# 08_FPGA_D.net
KiCad netlist of a schematic drawn in Altium Designer
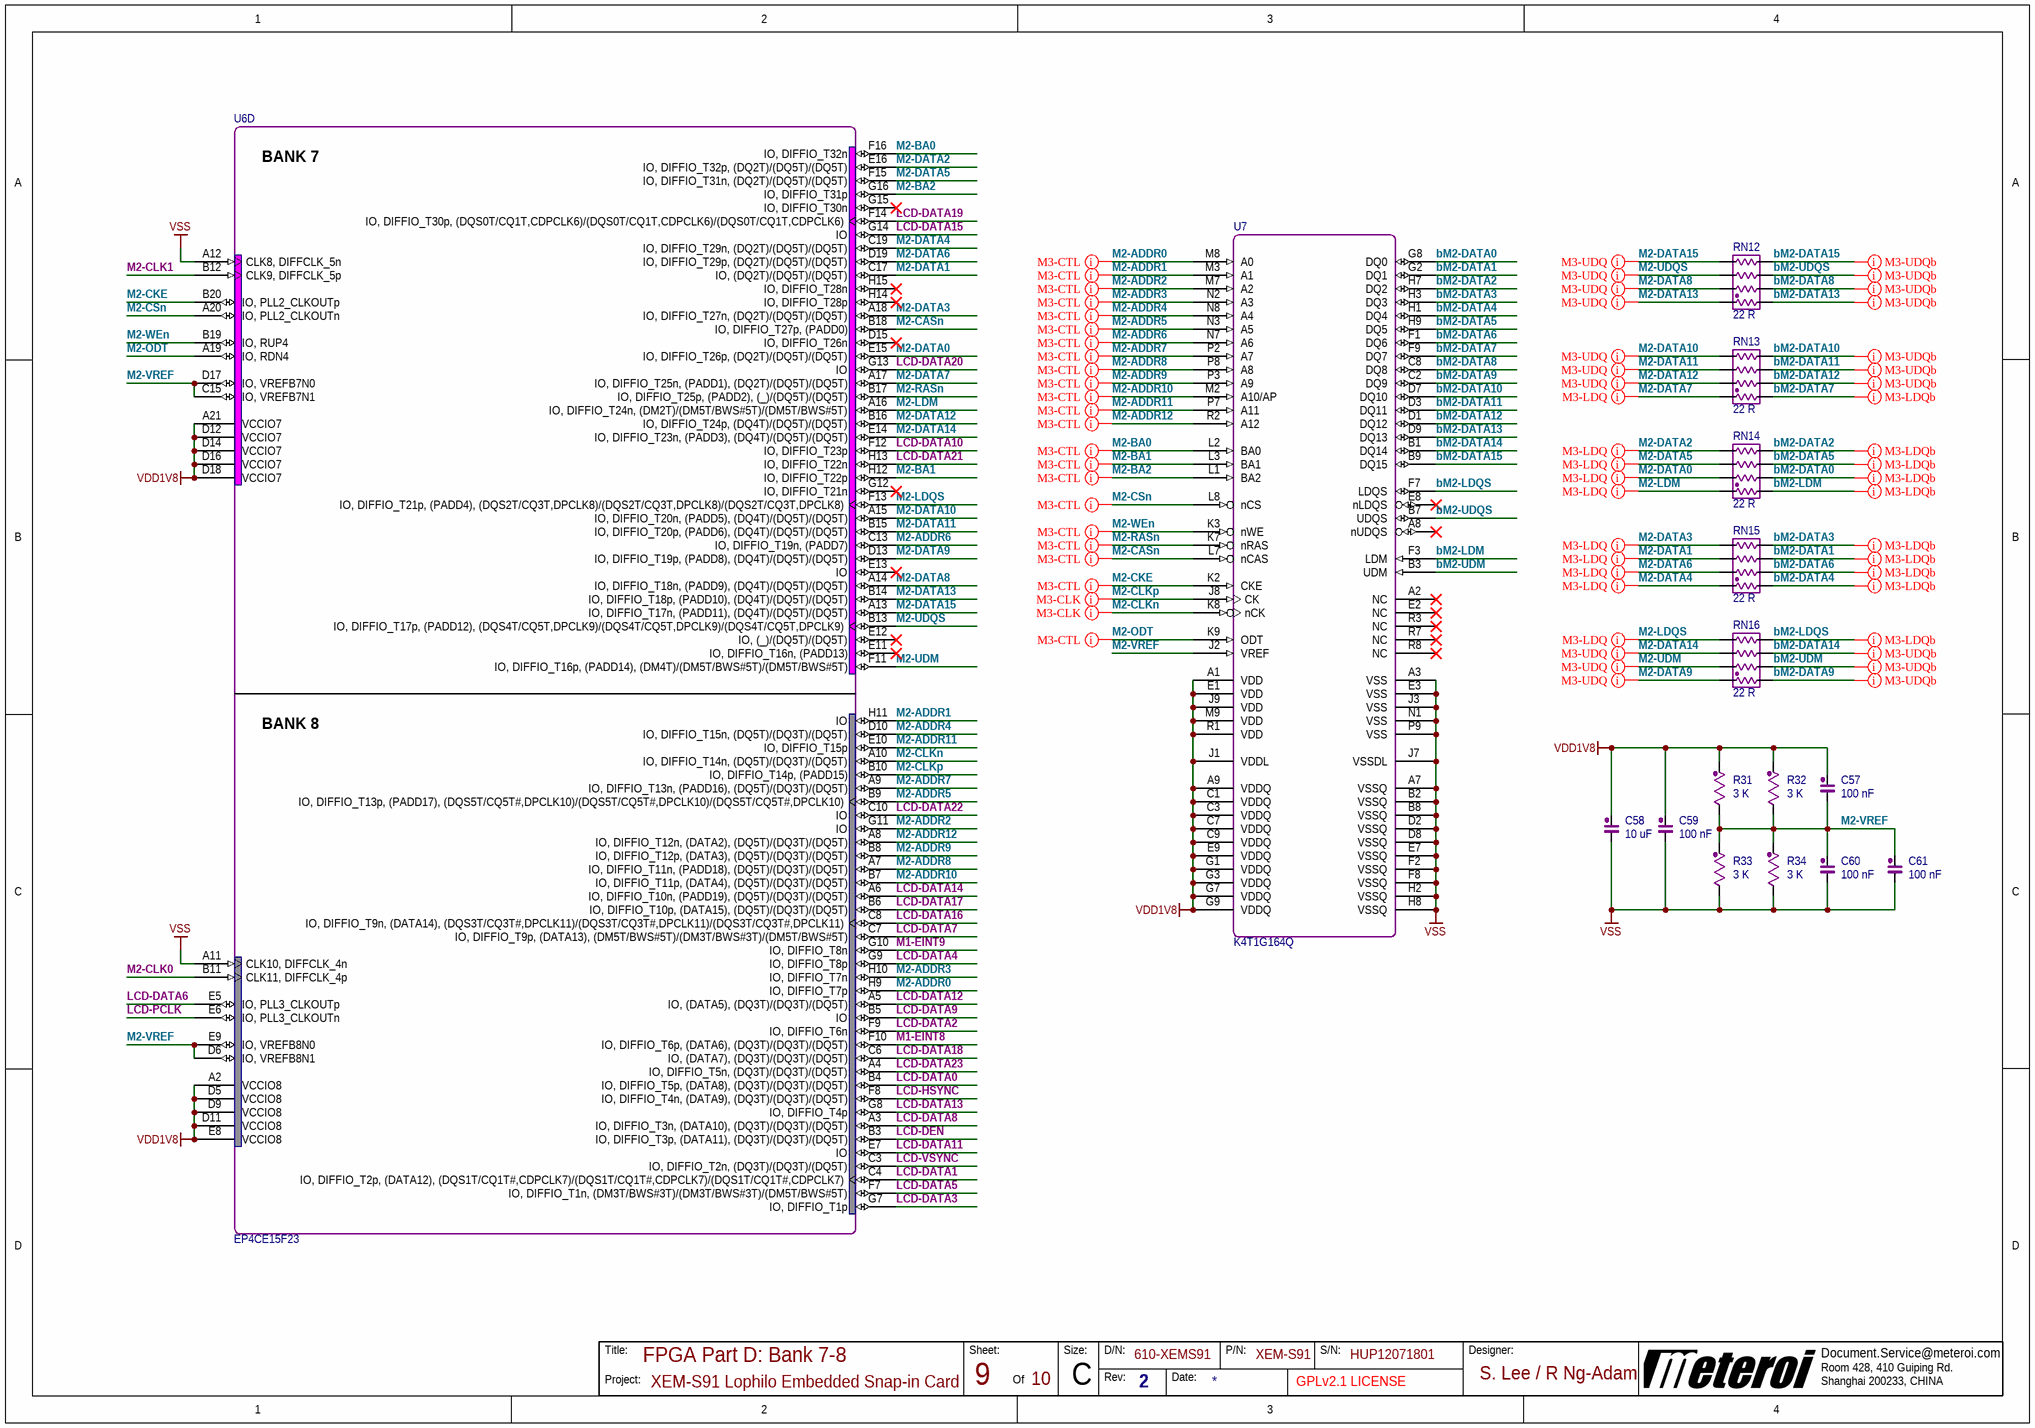
[diagram p0: 08_FPGA_D.SchDoc]

(export (version "E")
  (design (tool "Eeschema 10.0.6"))
  (components
    (comp (ref "C57")
      (value "100 nF")
      (footprint "0402A1")
      (description "Normal Capacitor")
      (fields
        (field (name "PARTNUMBER") "0")
        (field (name "PUBLISHER") "Cowin")
        (field (name "DESIGNER") "shyul")
      )
      (libsource (lib "Basc_1_Passive") (part "CAP"))
    )
    (comp (ref "C58")
      (value "10 uF")
      (footprint "0603A1")
      (description "Normal Capacitor")
      (fields
        (field (name "PARTNUMBER") "0")
        (field (name "PUBLISHER") "Cowin")
        (field (name "DESIGNER") "shyul")
      )
      (libsource (lib "Basc_1_Passive") (part "CAP"))
    )
    (comp (ref "C59")
      (value "100 nF")
      (footprint "0402A1")
      (description "Normal Capacitor")
      (fields
        (field (name "PARTNUMBER") "0")
        (field (name "PUBLISHER") "Cowin")
        (field (name "DESIGNER") "shyul")
      )
      (libsource (lib "Basc_1_Passive") (part "CAP"))
    )
    (comp (ref "C60")
      (value "100 nF")
      (footprint "0402A1")
      (description "Normal Capacitor")
      (fields
        (field (name "PARTNUMBER") "0")
        (field (name "PUBLISHER") "Cowin")
        (field (name "DESIGNER") "shyul")
      )
      (libsource (lib "Basc_1_Passive") (part "CAP"))
    )
    (comp (ref "C61")
      (value "100 nF")
      (footprint "0402BG")
      (description "Normal Capacitor")
      (fields
        (field (name "PARTNUMBER") "0")
        (field (name "PUBLISHER") "Cowin")
        (field (name "DESIGNER") "shyul")
      )
      (libsource (lib "Basc_1_Passive") (part "CAP"))
    )
    (comp (ref "R31")
      (value "3 K")
      (footprint "0402A2")
      (description "Normal Resistor")
      (fields
        (field (name "PARTNUMBER") "0")
        (field (name "DESIGNER") "shyul")
        (field (name "PUBLISHER") "Cowin")
      )
      (libsource (lib "Basc_1_Passive") (part "RES"))
    )
    (comp (ref "R32")
      (value "3 K")
      (footprint "0402A2")
      (description "Normal Resistor")
      (fields
        (field (name "PARTNUMBER") "0")
        (field (name "DESIGNER") "shyul")
        (field (name "PUBLISHER") "Cowin")
      )
      (libsource (lib "Basc_1_Passive") (part "RES"))
    )
    (comp (ref "R33")
      (value "3 K")
      (footprint "0402A2")
      (description "Normal Resistor")
      (fields
        (field (name "PARTNUMBER") "0")
        (field (name "DESIGNER") "shyul")
        (field (name "PUBLISHER") "Cowin")
      )
      (libsource (lib "Basc_1_Passive") (part "RES"))
    )
    (comp (ref "R34")
      (value "3 K")
      (footprint "0402A2")
      (description "Normal Resistor")
      (fields
        (field (name "PARTNUMBER") "0")
        (field (name "DESIGNER") "shyul")
        (field (name "PUBLISHER") "Cowin")
      )
      (libsource (lib "Basc_1_Passive") (part "RES"))
    )
    (comp (ref "RN12")
      (value "22 R")
      (footprint "0402PR4")
      (description "Resistor Array x4")
      (fields
        (field (name "PARTNUMBER") "YC124-JR-0722RL")
        (field (name "PUBLISHER") "Cowin")
        (field (name "DESIGNER") "shyul")
      )
      (libsource (lib "Basc_1_Passive") (part "RES_N4"))
    )
    (comp (ref "RN13")
      (value "22 R")
      (footprint "0402PR4")
      (description "Resistor Array x4")
      (fields
        (field (name "PARTNUMBER") "YC124-JR-0722RL")
        (field (name "PUBLISHER") "Cowin")
        (field (name "DESIGNER") "shyul")
      )
      (libsource (lib "Basc_1_Passive") (part "RES_N4"))
    )
    (comp (ref "RN14")
      (value "22 R")
      (footprint "0402PR4")
      (description "Resistor Array x4")
      (fields
        (field (name "PARTNUMBER") "YC124-JR-0722RL")
        (field (name "PUBLISHER") "Cowin")
        (field (name "DESIGNER") "shyul")
      )
      (libsource (lib "Basc_1_Passive") (part "RES_N4"))
    )
    (comp (ref "RN15")
      (value "22 R")
      (footprint "0402PR4")
      (description "Resistor Array x4")
      (fields
        (field (name "PARTNUMBER") "YC124-JR-0722RL")
        (field (name "PUBLISHER") "Cowin")
        (field (name "DESIGNER") "shyul")
      )
      (libsource (lib "Basc_1_Passive") (part "RES_N4"))
    )
    (comp (ref "RN16")
      (value "22 R")
      (footprint "0402PR4")
      (description "Resistor Array x4")
      (fields
        (field (name "PARTNUMBER") "YC124-JR-0722RL")
        (field (name "PUBLISHER") "Cowin")
        (field (name "DESIGNER") "shyul")
      )
      (libsource (lib "Basc_1_Passive") (part "RES_N4"))
    )
    (comp (ref "U6")
      (value "EP4CE15F23")
      (footprint "FBGA-484")
      (description "Cyclone IV EP4CE15F23 FPGA")
      (fields
        (field (name "PARTNUMBER") "EP4CE15F23C8N")
        (field (name "DESIGNER") "shyul")
        (field (name "PUBLISHER") "Cowin")
      )
      (libsource (lib "PCB_XEM-S91") (part "EP4CE15F23"))
    )
    (comp (ref "U7")
      (value "K4T1G164Q")
      (footprint "FBGA-DDR-84")
      (description "K4T1G164Q 64M x16 DDR2 SDRAM")
      (fields
        (field (name "PARTNUMBER") "K4T1G164QF-BCE7")
        (field (name "DESIGNER") "shyul")
        (field (name "PUBLISHER") "Cowin")
      )
      (libsource (lib "PCB_XEM-S91") (part "K4T1G164Q"))
    )
  )
  (nets
    (net (code "1") (name "/LCD-DATA0") (class "Default")
      (node (ref "U6") (pin "B4") (pinfunction "IO,_DIFFIO_T5p,_(DATA8),_(DQ3T)/(DQ3T)/(DQ5T)_B4") (pintype "bidirectional"))
    )
    (net (code "2") (name "/LCD-DATA1") (class "Default")
      (node (ref "U6") (pin "C4") (pinfunction "IO,_DIFFIO_T2p,_(DATA12),_(DQS1T/CQ1T#,CDPCLK7)/(DQS1T/CQ1T#,CDPCLK7)/(DQS1T/CQ1T#,CDPCLK7)_C4") (pintype "bidirectional"))
    )
    (net (code "3") (name "/LCD-DATA2") (class "Default")
      (node (ref "U6") (pin "F9") (pinfunction "IO,_DIFFIO_T6n_F9") (pintype "bidirectional"))
    )
    (net (code "4") (name "/LCD-DATA3") (class "Default")
      (node (ref "U6") (pin "G7") (pinfunction "IO,_DIFFIO_T1p_G7") (pintype "bidirectional"))
    )
    (net (code "5") (name "/LCD-DATA4") (class "Default")
      (node (ref "U6") (pin "G9") (pinfunction "IO,_DIFFIO_T8p_G9") (pintype "bidirectional"))
    )
    (net (code "6") (name "/LCD-DATA5") (class "Default")
      (node (ref "U6") (pin "F7") (pinfunction "IO,_DIFFIO_T1n,_(DM3T/BWS#3T)/(DM3T/BWS#3T)/(DM5T/BWS#5T)_F7") (pintype "bidirectional"))
    )
    (net (code "7") (name "/LCD-DATA6") (class "Default")
      (node (ref "U6") (pin "E5") (pinfunction "IO,_PLL3_CLKOUTp_E5") (pintype "bidirectional"))
    )
    (net (code "8") (name "/LCD-DATA7") (class "Default")
      (node (ref "U6") (pin "C7") (pinfunction "IO,_DIFFIO_T9p,_(DATA13),_(DM5T/BWS#5T)/(DM3T/BWS#3T)/(DM5T/BWS#5T)_C7") (pintype "bidirectional"))
    )
    (net (code "9") (name "/LCD-DATA8") (class "Default")
      (node (ref "U6") (pin "A3") (pinfunction "IO,_DIFFIO_T3n,_(DATA10),_(DQ3T)/(DQ3T)/(DQ5T)_A3") (pintype "bidirectional"))
    )
    (net (code "10") (name "/LCD-DATA9") (class "Default")
      (node (ref "U6") (pin "B5") (pinfunction "IO_B5") (pintype "bidirectional"))
    )
    (net (code "11") (name "/LCD-DATA10") (class "Default")
      (node (ref "U6") (pin "F12") (pinfunction "IO,_DIFFIO_T23p_F12") (pintype "bidirectional"))
    )
    (net (code "12") (name "/LCD-DATA11") (class "Default")
      (node (ref "U6") (pin "E7") (pinfunction "IO_E7") (pintype "bidirectional"))
    )
    (net (code "13") (name "/LCD-DATA12") (class "Default")
      (node (ref "U6") (pin "A5") (pinfunction "IO,_(DATA5),_(DQ3T)/(DQ3T)/(DQ5T)_A5") (pintype "bidirectional"))
    )
    (net (code "14") (name "/LCD-DATA13") (class "Default")
      (node (ref "U6") (pin "G8") (pinfunction "IO,_DIFFIO_T4p_G8") (pintype "bidirectional"))
    )
    (net (code "15") (name "/LCD-DATA14") (class "Default")
      (node (ref "U6") (pin "A6") (pinfunction "IO,_DIFFIO_T10n,_(PADD19),_(DQ5T)/(DQ3T)/(DQ5T)_A6") (pintype "bidirectional"))
    )
    (net (code "16") (name "/LCD-DATA15") (class "Default")
      (node (ref "U6") (pin "G14") (pinfunction "IO_G14") (pintype "bidirectional"))
    )
    (net (code "17") (name "/LCD-DATA16") (class "Default")
      (node (ref "U6") (pin "C8") (pinfunction "IO,_DIFFIO_T9n,_(DATA14),_(DQS3T/CQ3T#,DPCLK11)/(DQS3T/CQ3T#,DPCLK11)/(DQS3T/CQ3T#,DPCLK11)_C8") (pintype "bidirectional"))
    )
    (net (code "18") (name "/LCD-DATA17") (class "Default")
      (node (ref "U6") (pin "B6") (pinfunction "IO,_DIFFIO_T10p,_(DATA15),_(DQ5T)/(DQ3T)/(DQ5T)_B6") (pintype "bidirectional"))
    )
    (net (code "19") (name "/LCD-DATA18") (class "Default")
      (node (ref "U6") (pin "C6") (pinfunction "IO,_(DATA7),_(DQ3T)/(DQ3T)/(DQ5T)_C6") (pintype "bidirectional"))
    )
    (net (code "20") (name "/LCD-DATA19") (class "Default")
      (node (ref "U6") (pin "F14") (pinfunction "IO,_DIFFIO_T30p,_(DQS0T/CQ1T,CDPCLK6)/(DQS0T/CQ1T,CDPCLK6)/(DQS0T/CQ1T,CDPCLK6)_F14") (pintype "bidirectional"))
    )
    (net (code "21") (name "/LCD-DATA20") (class "Default")
      (node (ref "U6") (pin "G13") (pinfunction "IO_G13") (pintype "bidirectional"))
    )
    (net (code "22") (name "/LCD-DATA21") (class "Default")
      (node (ref "U6") (pin "H13") (pinfunction "IO,_DIFFIO_T22n_H13") (pintype "bidirectional"))
    )
    (net (code "23") (name "/LCD-DATA22") (class "Default")
      (node (ref "U6") (pin "C10") (pinfunction "IO_C10") (pintype "bidirectional"))
    )
    (net (code "24") (name "/LCD-DATA23") (class "Default")
      (node (ref "U6") (pin "A4") (pinfunction "IO,_DIFFIO_T5n,_(DQ3T)/(DQ3T)/(DQ5T)_A4") (pintype "bidirectional"))
    )
    (net (code "25") (name "/LCD-DEN") (class "Default")
      (node (ref "U6") (pin "B3") (pinfunction "IO,_DIFFIO_T3p,_(DATA11),_(DQ3T)/(DQ3T)/(DQ5T)_B3") (pintype "bidirectional"))
    )
    (net (code "26") (name "/LCD-HSYNC") (class "Default")
      (node (ref "U6") (pin "F8") (pinfunction "IO,_DIFFIO_T4n,_(DATA9),_(DQ3T)/(DQ3T)/(DQ5T)_F8") (pintype "bidirectional"))
    )
    (net (code "27") (name "/LCD-PCLK") (class "Default")
      (node (ref "U6") (pin "E6") (pinfunction "IO,_PLL3_CLKOUTn_E6") (pintype "bidirectional"))
    )
    (net (code "28") (name "/LCD-VSYNC") (class "Default")
      (node (ref "U6") (pin "C3") (pinfunction "IO,_DIFFIO_T2n,_(DQ3T)/(DQ3T)/(DQ5T)_C3") (pintype "bidirectional"))
    )
    (net (code "29") (name "/M1-EINT8") (class "Default")
      (node (ref "U6") (pin "F10") (pinfunction "IO,_DIFFIO_T6p,_(DATA6),_(DQ3T)/(DQ3T)/(DQ5T)_F10") (pintype "bidirectional"))
    )
    (net (code "30") (name "/M1-EINT9") (class "Default")
      (node (ref "U6") (pin "G10") (pinfunction "IO,_DIFFIO_T8n_G10") (pintype "bidirectional"))
    )
    (net (code "31") (name "/M2-ADDR0") (class "Default")
      (node (ref "U6") (pin "H9") (pinfunction "IO,_DIFFIO_T7p_H9") (pintype "bidirectional"))
      (node (ref "U7") (pin "M8") (pinfunction "A0_M8") (pintype "input"))
    )
    (net (code "32") (name "/M2-ADDR1") (class "Default")
      (node (ref "U6") (pin "H11") (pinfunction "IO_H11") (pintype "bidirectional"))
      (node (ref "U7") (pin "M3") (pinfunction "A1_M3") (pintype "input"))
    )
    (net (code "33") (name "/M2-ADDR2") (class "Default")
      (node (ref "U6") (pin "G11") (pinfunction "IO_G11") (pintype "bidirectional"))
      (node (ref "U7") (pin "M7") (pinfunction "A2_M7") (pintype "input"))
    )
    (net (code "34") (name "/M2-ADDR3") (class "Default")
      (node (ref "U6") (pin "H10") (pinfunction "IO,_DIFFIO_T7n_H10") (pintype "bidirectional"))
      (node (ref "U7") (pin "N2") (pinfunction "A3_N2") (pintype "input"))
    )
    (net (code "35") (name "/M2-ADDR4") (class "Default")
      (node (ref "U6") (pin "D10") (pinfunction "IO,_DIFFIO_T15n,_(DQ5T)/(DQ3T)/(DQ5T)_D10") (pintype "bidirectional"))
      (node (ref "U7") (pin "N8") (pinfunction "A4_N8") (pintype "input"))
    )
    (net (code "36") (name "/M2-ADDR5") (class "Default")
      (node (ref "U6") (pin "B9") (pinfunction "IO,_DIFFIO_T13p,_(PADD17),_(DQS5T/CQ5T#,DPCLK10)/(DQS5T/CQ5T#,DPCLK10)/(DQS5T/CQ5T#,DPCLK10)_B9") (pintype "bidirectional"))
      (node (ref "U7") (pin "N3") (pinfunction "A5_N3") (pintype "input"))
    )
    (net (code "37") (name "/M2-ADDR6") (class "Default")
      (node (ref "U6") (pin "C13") (pinfunction "IO,_DIFFIO_T19n,_(PADD7)_C13") (pintype "bidirectional"))
      (node (ref "U7") (pin "N7") (pinfunction "A6_N7") (pintype "input"))
    )
    (net (code "38") (name "/M2-ADDR7") (class "Default")
      (node (ref "U6") (pin "A9") (pinfunction "IO,_DIFFIO_T13n,_(PADD16),_(DQ5T)/(DQ3T)/(DQ5T)_A9") (pintype "bidirectional"))
      (node (ref "U7") (pin "P2") (pinfunction "A7_P2") (pintype "input"))
    )
    (net (code "39") (name "/M2-ADDR8") (class "Default")
      (node (ref "U6") (pin "A7") (pinfunction "IO,_DIFFIO_T11n,_(PADD18),_(DQ5T)/(DQ3T)/(DQ5T)_A7") (pintype "bidirectional"))
      (node (ref "U7") (pin "P8") (pinfunction "A8_P8") (pintype "input"))
    )
    (net (code "40") (name "/M2-ADDR9") (class "Default")
      (node (ref "U6") (pin "B8") (pinfunction "IO,_DIFFIO_T12p,_(DATA3),_(DQ5T)/(DQ3T)/(DQ5T)_B8") (pintype "bidirectional"))
      (node (ref "U7") (pin "P3") (pinfunction "A9_P3") (pintype "input"))
    )
    (net (code "41") (name "/M2-ADDR10") (class "Default")
      (node (ref "U6") (pin "B7") (pinfunction "IO,_DIFFIO_T11p,_(DATA4),_(DQ5T)/(DQ3T)/(DQ5T)_B7") (pintype "bidirectional"))
      (node (ref "U7") (pin "M2") (pinfunction "A10/AP_M2") (pintype "input"))
    )
    (net (code "42") (name "/M2-ADDR11") (class "Default")
      (node (ref "U6") (pin "E10") (pinfunction "IO,_DIFFIO_T15p_E10") (pintype "bidirectional"))
      (node (ref "U7") (pin "P7") (pinfunction "A11_P7") (pintype "input"))
    )
    (net (code "43") (name "/M2-ADDR12") (class "Default")
      (node (ref "U6") (pin "A8") (pinfunction "IO,_DIFFIO_T12n,_(DATA2),_(DQ5T)/(DQ3T)/(DQ5T)_A8") (pintype "bidirectional"))
      (node (ref "U7") (pin "R2") (pinfunction "A12_R2") (pintype "input"))
    )
    (net (code "44") (name "/M2-BA0") (class "Default")
      (node (ref "U6") (pin "F16") (pinfunction "IO,_DIFFIO_T32n_F16") (pintype "bidirectional"))
      (node (ref "U7") (pin "L2") (pinfunction "BA0_L2") (pintype "input"))
    )
    (net (code "45") (name "/M2-BA1") (class "Default")
      (node (ref "U6") (pin "H12") (pinfunction "IO,_DIFFIO_T22p_H12") (pintype "bidirectional"))
      (node (ref "U7") (pin "L3") (pinfunction "BA1_L3") (pintype "input"))
    )
    (net (code "46") (name "/M2-BA2") (class "Default")
      (node (ref "U6") (pin "G16") (pinfunction "IO,_DIFFIO_T31p_G16") (pintype "bidirectional"))
      (node (ref "U7") (pin "L1") (pinfunction "BA2_L1") (pintype "input"))
    )
    (net (code "47") (name "/M2-CASn") (class "Default")
      (node (ref "U6") (pin "B18") (pinfunction "IO,_DIFFIO_T27p,_(PADD0)_B18") (pintype "bidirectional"))
      (node (ref "U7") (pin "L7") (pinfunction "nCAS_L7") (pintype "input"))
    )
    (net (code "48") (name "/M2-CKE") (class "Default")
      (node (ref "U6") (pin "B20") (pinfunction "IO,_PLL2_CLKOUTp_B20") (pintype "bidirectional"))
      (node (ref "U7") (pin "K2") (pinfunction "CKE_K2") (pintype "input"))
    )
    (net (code "49") (name "/M2-CLK0") (class "Default")
      (node (ref "U6") (pin "B11") (pinfunction "CLK11,_DIFFCLK_4p_B11") (pintype "input"))
    )
    (net (code "50") (name "/M2-CLK1") (class "Default")
      (node (ref "U6") (pin "B12") (pinfunction "CLK9,_DIFFCLK_5p_B12") (pintype "input"))
    )
    (net (code "51") (name "/M2-CLKn") (class "Default")
      (node (ref "U6") (pin "A10") (pinfunction "IO,_DIFFIO_T14n,_(DQ5T)/(DQ3T)/(DQ5T)_A10") (pintype "bidirectional"))
      (node (ref "U7") (pin "K8") (pinfunction "nCK_K8") (pintype "input"))
    )
    (net (code "52") (name "/M2-CLKp") (class "Default")
      (node (ref "U6") (pin "B10") (pinfunction "IO,_DIFFIO_T14p,_(PADD15)_B10") (pintype "bidirectional"))
      (node (ref "U7") (pin "J8") (pinfunction "CK_J8") (pintype "input"))
    )
    (net (code "53") (name "/M2-CSn") (class "Default")
      (node (ref "U6") (pin "A20") (pinfunction "IO,_PLL2_CLKOUTn_A20") (pintype "bidirectional"))
      (node (ref "U7") (pin "L8") (pinfunction "nCS_L8") (pintype "input"))
    )
    (net (code "54") (name "/M2-DATA0") (class "Default")
      (node (ref "RN14") (pin "3") (pinfunction "3_3") (pintype "passive"))
      (node (ref "U6") (pin "E15") (pinfunction "IO,_DIFFIO_T26p,_(DQ2T)/(DQ5T)/(DQ5T)_E15") (pintype "bidirectional"))
    )
    (net (code "55") (name "/M2-DATA1") (class "Default")
      (node (ref "RN15") (pin "5") (pinfunction "5_5") (pintype "passive"))
      (node (ref "U6") (pin "C17") (pinfunction "IO,_(DQ2T)/(DQ5T)/(DQ5T)_C17") (pintype "bidirectional"))
    )
    (net (code "56") (name "/M2-DATA2") (class "Default")
      (node (ref "RN14") (pin "7") (pinfunction "7_7") (pintype "passive"))
      (node (ref "U6") (pin "E16") (pinfunction "IO,_DIFFIO_T32p,_(DQ2T)/(DQ5T)/(DQ5T)_E16") (pintype "bidirectional"))
    )
    (net (code "57") (name "/M2-DATA3") (class "Default")
      (node (ref "RN15") (pin "7") (pinfunction "7_7") (pintype "passive"))
      (node (ref "U6") (pin "A18") (pinfunction "IO,_DIFFIO_T27n,_(DQ2T)/(DQ5T)/(DQ5T)_A18") (pintype "bidirectional"))
    )
    (net (code "58") (name "/M2-DATA4") (class "Default")
      (node (ref "RN15") (pin "1") (pinfunction "1_1") (pintype "passive"))
      (node (ref "U6") (pin "C19") (pinfunction "IO,_DIFFIO_T29n,_(DQ2T)/(DQ5T)/(DQ5T)_C19") (pintype "bidirectional"))
    )
    (net (code "59") (name "/M2-DATA5") (class "Default")
      (node (ref "RN14") (pin "5") (pinfunction "5_5") (pintype "passive"))
      (node (ref "U6") (pin "F15") (pinfunction "IO,_DIFFIO_T31n,_(DQ2T)/(DQ5T)/(DQ5T)_F15") (pintype "bidirectional"))
    )
    (net (code "60") (name "/M2-DATA6") (class "Default")
      (node (ref "RN15") (pin "3") (pinfunction "3_3") (pintype "passive"))
      (node (ref "U6") (pin "D19") (pinfunction "IO,_DIFFIO_T29p,_(DQ2T)/(DQ5T)/(DQ5T)_D19") (pintype "bidirectional"))
    )
    (net (code "61") (name "/M2-DATA7") (class "Default")
      (node (ref "RN13") (pin "1") (pinfunction "1_1") (pintype "passive"))
      (node (ref "U6") (pin "A17") (pinfunction "IO,_DIFFIO_T25n,_(PADD1),_(DQ2T)/(DQ5T)/(DQ5T)_A17") (pintype "bidirectional"))
    )
    (net (code "62") (name "/M2-DATA8") (class "Default")
      (node (ref "RN12") (pin "3") (pinfunction "3_3") (pintype "passive"))
      (node (ref "U6") (pin "A14") (pinfunction "IO,_DIFFIO_T18n,_(PADD9),_(DQ4T)/(DQ5T)/(DQ5T)_A14") (pintype "bidirectional"))
    )
    (net (code "63") (name "/M2-DATA9") (class "Default")
      (node (ref "RN16") (pin "1") (pinfunction "1_1") (pintype "passive"))
      (node (ref "U6") (pin "D13") (pinfunction "IO,_DIFFIO_T19p,_(PADD8),_(DQ4T)/(DQ5T)/(DQ5T)_D13") (pintype "bidirectional"))
    )
    (net (code "64") (name "/M2-DATA10") (class "Default")
      (node (ref "RN13") (pin "7") (pinfunction "7_7") (pintype "passive"))
      (node (ref "U6") (pin "A15") (pinfunction "IO,_DIFFIO_T20n,_(PADD5),_(DQ4T)/(DQ5T)/(DQ5T)_A15") (pintype "bidirectional"))
    )
    (net (code "65") (name "/M2-DATA11") (class "Default")
      (node (ref "RN13") (pin "5") (pinfunction "5_5") (pintype "passive"))
      (node (ref "U6") (pin "B15") (pinfunction "IO,_DIFFIO_T20p,_(PADD6),_(DQ4T)/(DQ5T)/(DQ5T)_B15") (pintype "bidirectional"))
    )
    (net (code "66") (name "/M2-DATA12") (class "Default")
      (node (ref "RN13") (pin "3") (pinfunction "3_3") (pintype "passive"))
      (node (ref "U6") (pin "B16") (pinfunction "IO,_DIFFIO_T24p,_(DQ4T)/(DQ5T)/(DQ5T)_B16") (pintype "bidirectional"))
    )
    (net (code "67") (name "/M2-DATA13") (class "Default")
      (node (ref "RN12") (pin "1") (pinfunction "1_1") (pintype "passive"))
      (node (ref "U6") (pin "B14") (pinfunction "IO,_DIFFIO_T18p,_(PADD10),_(DQ4T)/(DQ5T)/(DQ5T)_B14") (pintype "bidirectional"))
    )
    (net (code "68") (name "/M2-DATA14") (class "Default")
      (node (ref "RN16") (pin "5") (pinfunction "5_5") (pintype "passive"))
      (node (ref "U6") (pin "E14") (pinfunction "IO,_DIFFIO_T23n,_(PADD3),_(DQ4T)/(DQ5T)/(DQ5T)_E14") (pintype "bidirectional"))
    )
    (net (code "69") (name "/M2-DATA15") (class "Default")
      (node (ref "RN12") (pin "7") (pinfunction "7_7") (pintype "passive"))
      (node (ref "U6") (pin "A13") (pinfunction "IO,_DIFFIO_T17n,_(PADD11),_(DQ4T)/(DQ5T)/(DQ5T)_A13") (pintype "bidirectional"))
    )
    (net (code "70") (name "/M2-LDM") (class "Default")
      (node (ref "RN14") (pin "1") (pinfunction "1_1") (pintype "passive"))
      (node (ref "U6") (pin "A16") (pinfunction "IO,_DIFFIO_T24n,_(DM2T)/(DM5T/BWS#5T)/(DM5T/BWS#5T)_A16") (pintype "bidirectional"))
    )
    (net (code "71") (name "/M2-LDQS") (class "Default")
      (node (ref "RN16") (pin "7") (pinfunction "7_7") (pintype "passive"))
      (node (ref "U6") (pin "F13") (pinfunction "IO,_DIFFIO_T21p,_(PADD4),_(DQS2T/CQ3T,DPCLK8)/(DQS2T/CQ3T,DPCLK8)/(DQS2T/CQ3T,DPCLK8)_F13") (pintype "bidirectional"))
    )
    (net (code "72") (name "/M2-ODT") (class "Default")
      (node (ref "U6") (pin "A19") (pinfunction "IO,_RDN4_A19") (pintype "bidirectional"))
      (node (ref "U7") (pin "K9") (pinfunction "ODT_K9") (pintype "input"))
    )
    (net (code "73") (name "/M2-RASn") (class "Default")
      (node (ref "U6") (pin "B17") (pinfunction "IO,_DIFFIO_T25p,_(PADD2),_(_)/(DQ5T)/(DQ5T)_B17") (pintype "bidirectional"))
      (node (ref "U7") (pin "K7") (pinfunction "nRAS_K7") (pintype "input"))
    )
    (net (code "74") (name "/M2-UDM") (class "Default")
      (node (ref "RN16") (pin "3") (pinfunction "3_3") (pintype "passive"))
      (node (ref "U6") (pin "F11") (pinfunction "IO,_DIFFIO_T16p,_(PADD14),_(DM4T)/(DM5T/BWS#5T)/(DM5T/BWS#5T)_F11") (pintype "bidirectional"))
    )
    (net (code "75") (name "/M2-UDQS") (class "Default")
      (node (ref "RN12") (pin "5") (pinfunction "5_5") (pintype "passive"))
      (node (ref "U6") (pin "B13") (pinfunction "IO,_DIFFIO_T17p,_(PADD12),_(DQS4T/CQ5T,DPCLK9)/(DQS4T/CQ5T,DPCLK9)/(DQS4T/CQ5T,DPCLK9)_B13") (pintype "bidirectional"))
    )
    (net (code "76") (name "/M2-VREF") (class "Default")
      (node (ref "C57") (pin "1") (pinfunction "1_1") (pintype "passive"))
      (node (ref "C60") (pin "2") (pinfunction "2_2") (pintype "passive"))
      (node (ref "C61") (pin "2") (pinfunction "2_2") (pintype "passive"))
      (node (ref "R31") (pin "1") (pinfunction "1_1") (pintype "passive"))
      (node (ref "R32") (pin "1") (pinfunction "1_1") (pintype "passive"))
      (node (ref "R33") (pin "2") (pinfunction "2_2") (pintype "passive"))
      (node (ref "R34") (pin "2") (pinfunction "2_2") (pintype "passive"))
      (node (ref "U6") (pin "C15") (pinfunction "IO,_VREFB7N1_C15") (pintype "bidirectional"))
      (node (ref "U6") (pin "D17") (pinfunction "IO,_VREFB7N0_D17") (pintype "bidirectional"))
      (node (ref "U6") (pin "D6") (pinfunction "IO,_VREFB8N1_D6") (pintype "bidirectional"))
      (node (ref "U6") (pin "E9") (pinfunction "IO,_VREFB8N0_E9") (pintype "bidirectional"))
      (node (ref "U7") (pin "J2") (pinfunction "VREF_J2") (pintype "input"))
    )
    (net (code "77") (name "/M2-WEn") (class "Default")
      (node (ref "U6") (pin "B19") (pinfunction "IO,_RUP4_B19") (pintype "bidirectional"))
      (node (ref "U7") (pin "K3") (pinfunction "nWE_K3") (pintype "input"))
    )
    (net (code "78") (name "/bM2-DATA0") (class "Default")
      (node (ref "RN14") (pin "4") (pinfunction "4_4") (pintype "passive"))
      (node (ref "U7") (pin "G8") (pinfunction "DQ0_G8") (pintype "bidirectional"))
    )
    (net (code "79") (name "/bM2-DATA1") (class "Default")
      (node (ref "RN15") (pin "6") (pinfunction "6_6") (pintype "passive"))
      (node (ref "U7") (pin "G2") (pinfunction "DQ1_G2") (pintype "bidirectional"))
    )
    (net (code "80") (name "/bM2-DATA2") (class "Default")
      (node (ref "RN14") (pin "8") (pinfunction "8_8") (pintype "passive"))
      (node (ref "U7") (pin "H7") (pinfunction "DQ2_H7") (pintype "bidirectional"))
    )
    (net (code "81") (name "/bM2-DATA3") (class "Default")
      (node (ref "RN15") (pin "8") (pinfunction "8_8") (pintype "passive"))
      (node (ref "U7") (pin "H3") (pinfunction "DQ3_H3") (pintype "bidirectional"))
    )
    (net (code "82") (name "/bM2-DATA4") (class "Default")
      (node (ref "RN15") (pin "2") (pinfunction "2_2") (pintype "passive"))
      (node (ref "U7") (pin "H1") (pinfunction "DQ4_H1") (pintype "bidirectional"))
    )
    (net (code "83") (name "/bM2-DATA5") (class "Default")
      (node (ref "RN14") (pin "6") (pinfunction "6_6") (pintype "passive"))
      (node (ref "U7") (pin "H9") (pinfunction "DQ5_H9") (pintype "bidirectional"))
    )
    (net (code "84") (name "/bM2-DATA6") (class "Default")
      (node (ref "RN15") (pin "4") (pinfunction "4_4") (pintype "passive"))
      (node (ref "U7") (pin "F1") (pinfunction "DQ6_F1") (pintype "bidirectional"))
    )
    (net (code "85") (name "/bM2-DATA7") (class "Default")
      (node (ref "RN13") (pin "2") (pinfunction "2_2") (pintype "passive"))
      (node (ref "U7") (pin "F9") (pinfunction "DQ7_F9") (pintype "bidirectional"))
    )
    (net (code "86") (name "/bM2-DATA8") (class "Default")
      (node (ref "RN12") (pin "4") (pinfunction "4_4") (pintype "passive"))
      (node (ref "U7") (pin "C8") (pinfunction "DQ8_C8") (pintype "bidirectional"))
    )
    (net (code "87") (name "/bM2-DATA9") (class "Default")
      (node (ref "RN16") (pin "2") (pinfunction "2_2") (pintype "passive"))
      (node (ref "U7") (pin "C2") (pinfunction "DQ9_C2") (pintype "bidirectional"))
    )
    (net (code "88") (name "/bM2-DATA10") (class "Default")
      (node (ref "RN13") (pin "8") (pinfunction "8_8") (pintype "passive"))
      (node (ref "U7") (pin "D7") (pinfunction "DQ10_D7") (pintype "bidirectional"))
    )
    (net (code "89") (name "/bM2-DATA11") (class "Default")
      (node (ref "RN13") (pin "6") (pinfunction "6_6") (pintype "passive"))
      (node (ref "U7") (pin "D3") (pinfunction "DQ11_D3") (pintype "bidirectional"))
    )
    (net (code "90") (name "/bM2-DATA12") (class "Default")
      (node (ref "RN13") (pin "4") (pinfunction "4_4") (pintype "passive"))
      (node (ref "U7") (pin "D1") (pinfunction "DQ12_D1") (pintype "bidirectional"))
    )
    (net (code "91") (name "/bM2-DATA13") (class "Default")
      (node (ref "RN12") (pin "2") (pinfunction "2_2") (pintype "passive"))
      (node (ref "U7") (pin "D9") (pinfunction "DQ13_D9") (pintype "bidirectional"))
    )
    (net (code "92") (name "/bM2-DATA14") (class "Default")
      (node (ref "RN16") (pin "6") (pinfunction "6_6") (pintype "passive"))
      (node (ref "U7") (pin "B1") (pinfunction "DQ14_B1") (pintype "bidirectional"))
    )
    (net (code "93") (name "/bM2-DATA15") (class "Default")
      (node (ref "RN12") (pin "8") (pinfunction "8_8") (pintype "passive"))
      (node (ref "U7") (pin "B9") (pinfunction "DQ15_B9") (pintype "bidirectional"))
    )
    (net (code "94") (name "/bM2-LDM") (class "Default")
      (node (ref "RN14") (pin "2") (pinfunction "2_2") (pintype "passive"))
      (node (ref "U7") (pin "F3") (pinfunction "LDM_F3") (pintype "input"))
    )
    (net (code "95") (name "/bM2-LDQS") (class "Default")
      (node (ref "RN16") (pin "8") (pinfunction "8_8") (pintype "passive"))
      (node (ref "U7") (pin "F7") (pinfunction "LDQS_F7") (pintype "bidirectional"))
    )
    (net (code "96") (name "/bM2-UDM") (class "Default")
      (node (ref "RN16") (pin "4") (pinfunction "4_4") (pintype "passive"))
      (node (ref "U7") (pin "B3") (pinfunction "UDM_B3") (pintype "input"))
    )
    (net (code "97") (name "/bM2-UDQS") (class "Default")
      (node (ref "RN12") (pin "6") (pinfunction "6_6") (pintype "passive"))
      (node (ref "U7") (pin "B7") (pinfunction "UDQS_B7") (pintype "bidirectional"))
    )
    (net (code "98") (name "VDD1V8") (class "Default")
      (node (ref "C57") (pin "2") (pinfunction "2_2") (pintype "passive"))
      (node (ref "C58") (pin "2") (pinfunction "2_2") (pintype "passive"))
      (node (ref "C59") (pin "2") (pinfunction "2_2") (pintype "passive"))
      (node (ref "R31") (pin "2") (pinfunction "2_2") (pintype "passive"))
      (node (ref "R32") (pin "2") (pinfunction "2_2") (pintype "passive"))
      (node (ref "U6") (pin "A2") (pinfunction "VCCIO8_A2") (pintype "power_in"))
      (node (ref "U6") (pin "A21") (pinfunction "VCCIO7_A21") (pintype "power_in"))
      (node (ref "U6") (pin "D11") (pinfunction "VCCIO8_D11") (pintype "power_in"))
      (node (ref "U6") (pin "D12") (pinfunction "VCCIO7_D12") (pintype "power_in"))
      (node (ref "U6") (pin "D14") (pinfunction "VCCIO7_D14") (pintype "power_in"))
      (node (ref "U6") (pin "D16") (pinfunction "VCCIO7_D16") (pintype "power_in"))
      (node (ref "U6") (pin "D18") (pinfunction "VCCIO7_D18") (pintype "power_in"))
      (node (ref "U6") (pin "D5") (pinfunction "VCCIO8_D5") (pintype "power_in"))
      (node (ref "U6") (pin "D9") (pinfunction "VCCIO8_D9") (pintype "power_in"))
      (node (ref "U6") (pin "E8") (pinfunction "VCCIO8_E8") (pintype "power_in"))
      (node (ref "U7") (pin "A1") (pinfunction "VDD_A1") (pintype "passive"))
      (node (ref "U7") (pin "A9") (pinfunction "VDDQ_A9") (pintype "passive"))
      (node (ref "U7") (pin "C1") (pinfunction "VDDQ_C1") (pintype "passive"))
      (node (ref "U7") (pin "C3") (pinfunction "VDDQ_C3") (pintype "passive"))
      (node (ref "U7") (pin "C7") (pinfunction "VDDQ_C7") (pintype "passive"))
      (node (ref "U7") (pin "C9") (pinfunction "VDDQ_C9") (pintype "passive"))
      (node (ref "U7") (pin "E1") (pinfunction "VDD_E1") (pintype "passive"))
      (node (ref "U7") (pin "E9") (pinfunction "VDDQ_E9") (pintype "passive"))
      (node (ref "U7") (pin "G1") (pinfunction "VDDQ_G1") (pintype "passive"))
      (node (ref "U7") (pin "G3") (pinfunction "VDDQ_G3") (pintype "passive"))
      (node (ref "U7") (pin "G7") (pinfunction "VDDQ_G7") (pintype "passive"))
      (node (ref "U7") (pin "G9") (pinfunction "VDDQ_G9") (pintype "passive"))
      (node (ref "U7") (pin "J1") (pinfunction "VDDL_J1") (pintype "passive"))
      (node (ref "U7") (pin "J9") (pinfunction "VDD_J9") (pintype "passive"))
      (node (ref "U7") (pin "M9") (pinfunction "VDD_M9") (pintype "passive"))
      (node (ref "U7") (pin "R1") (pinfunction "VDD_R1") (pintype "passive"))
    )
    (net (code "99") (name "VSS") (class "Default")
      (node (ref "C58") (pin "1") (pinfunction "1_1") (pintype "passive"))
      (node (ref "C59") (pin "1") (pinfunction "1_1") (pintype "passive"))
      (node (ref "C60") (pin "1") (pinfunction "1_1") (pintype "passive"))
      (node (ref "C61") (pin "1") (pinfunction "1_1") (pintype "passive"))
      (node (ref "R33") (pin "1") (pinfunction "1_1") (pintype "passive"))
      (node (ref "R34") (pin "1") (pinfunction "1_1") (pintype "passive"))
      (node (ref "U6") (pin "A11") (pinfunction "CLK10,_DIFFCLK_4n_A11") (pintype "input"))
      (node (ref "U6") (pin "A12") (pinfunction "CLK8,_DIFFCLK_5n_A12") (pintype "input"))
      (node (ref "U7") (pin "A3") (pinfunction "VSS_A3") (pintype "passive"))
      (node (ref "U7") (pin "A7") (pinfunction "VSSQ_A7") (pintype "passive"))
      (node (ref "U7") (pin "B2") (pinfunction "VSSQ_B2") (pintype "passive"))
      (node (ref "U7") (pin "B8") (pinfunction "VSSQ_B8") (pintype "passive"))
      (node (ref "U7") (pin "D2") (pinfunction "VSSQ_D2") (pintype "passive"))
      (node (ref "U7") (pin "D8") (pinfunction "VSSQ_D8") (pintype "passive"))
      (node (ref "U7") (pin "E3") (pinfunction "VSS_E3") (pintype "passive"))
      (node (ref "U7") (pin "E7") (pinfunction "VSSQ_E7") (pintype "passive"))
      (node (ref "U7") (pin "F2") (pinfunction "VSSQ_F2") (pintype "passive"))
      (node (ref "U7") (pin "F8") (pinfunction "VSSQ_F8") (pintype "passive"))
      (node (ref "U7") (pin "H2") (pinfunction "VSSQ_H2") (pintype "passive"))
      (node (ref "U7") (pin "H8") (pinfunction "VSSQ_H8") (pintype "passive"))
      (node (ref "U7") (pin "J3") (pinfunction "VSS_J3") (pintype "passive"))
      (node (ref "U7") (pin "J7") (pinfunction "VSSDL_J7") (pintype "passive"))
      (node (ref "U7") (pin "N1") (pinfunction "VSS_N1") (pintype "passive"))
      (node (ref "U7") (pin "P9") (pinfunction "VSS_P9") (pintype "passive"))
    )
    (net (code "100") (name "unconnected-(U6D-IO,_(_){slash}(DQ5T){slash}(DQ5T)-PadE12)") (class "Default")
      (node (ref "U6") (pin "E12") (pinfunction "IO,_(_)/(DQ5T)/(DQ5T)_E12") (pintype "bidirectional+no_connect"))
    )
    (net (code "101") (name "unconnected-(U6D-IO,_DIFFIO_T16n,_(PADD13)-PadE11)") (class "Default")
      (node (ref "U6") (pin "E11") (pinfunction "IO,_DIFFIO_T16n,_(PADD13)_E11") (pintype "bidirectional+no_connect"))
    )
    (net (code "102") (name "unconnected-(U6D-IO,_DIFFIO_T21n-PadG12)") (class "Default")
      (node (ref "U6") (pin "G12") (pinfunction "IO,_DIFFIO_T21n_G12") (pintype "bidirectional+no_connect"))
    )
    (net (code "103") (name "unconnected-(U6D-IO,_DIFFIO_T26n-PadD15)") (class "Default")
      (node (ref "U6") (pin "D15") (pinfunction "IO,_DIFFIO_T26n_D15") (pintype "bidirectional+no_connect"))
    )
    (net (code "104") (name "unconnected-(U6D-IO,_DIFFIO_T28n-PadH15)") (class "Default")
      (node (ref "U6") (pin "H15") (pinfunction "IO,_DIFFIO_T28n_H15") (pintype "bidirectional+no_connect"))
    )
    (net (code "105") (name "unconnected-(U6D-IO,_DIFFIO_T28p-PadH14)") (class "Default")
      (node (ref "U6") (pin "H14") (pinfunction "IO,_DIFFIO_T28p_H14") (pintype "bidirectional+no_connect"))
    )
    (net (code "106") (name "unconnected-(U6D-IO,_DIFFIO_T30n-PadG15)") (class "Default")
      (node (ref "U6") (pin "G15") (pinfunction "IO,_DIFFIO_T30n_G15") (pintype "bidirectional+no_connect"))
    )
    (net (code "107") (name "unconnected-(U6D-IO-PadE13)") (class "Default")
      (node (ref "U6") (pin "E13") (pinfunction "IO_E13") (pintype "bidirectional+no_connect"))
    )
    (net (code "108") (name "unconnected-(U7-NC-PadA2)") (class "Default")
      (node (ref "U7") (pin "A2") (pinfunction "NC_A2") (pintype "passive+no_connect"))
    )
    (net (code "109") (name "unconnected-(U7-NC-PadE2)") (class "Default")
      (node (ref "U7") (pin "E2") (pinfunction "NC_E2") (pintype "passive+no_connect"))
    )
    (net (code "110") (name "unconnected-(U7-NC-PadR3)") (class "Default")
      (node (ref "U7") (pin "R3") (pinfunction "NC_R3") (pintype "passive+no_connect"))
    )
    (net (code "111") (name "unconnected-(U7-NC-PadR7)") (class "Default")
      (node (ref "U7") (pin "R7") (pinfunction "NC_R7") (pintype "passive+no_connect"))
    )
    (net (code "112") (name "unconnected-(U7-NC-PadR8)") (class "Default")
      (node (ref "U7") (pin "R8") (pinfunction "NC_R8") (pintype "passive+no_connect"))
    )
    (net (code "113") (name "unconnected-(U7-nLDQS-PadE8)") (class "Default")
      (node (ref "U7") (pin "E8") (pinfunction "nLDQS_E8") (pintype "bidirectional+no_connect"))
    )
    (net (code "114") (name "unconnected-(U7-nUDQS-PadA8)") (class "Default")
      (node (ref "U7") (pin "A8") (pinfunction "nUDQS_A8") (pintype "bidirectional+no_connect"))
    )
  )
)
